# 1-Schematic_SmartTracker.net
KiCad netlist of a schematic drawn in EasyEDA
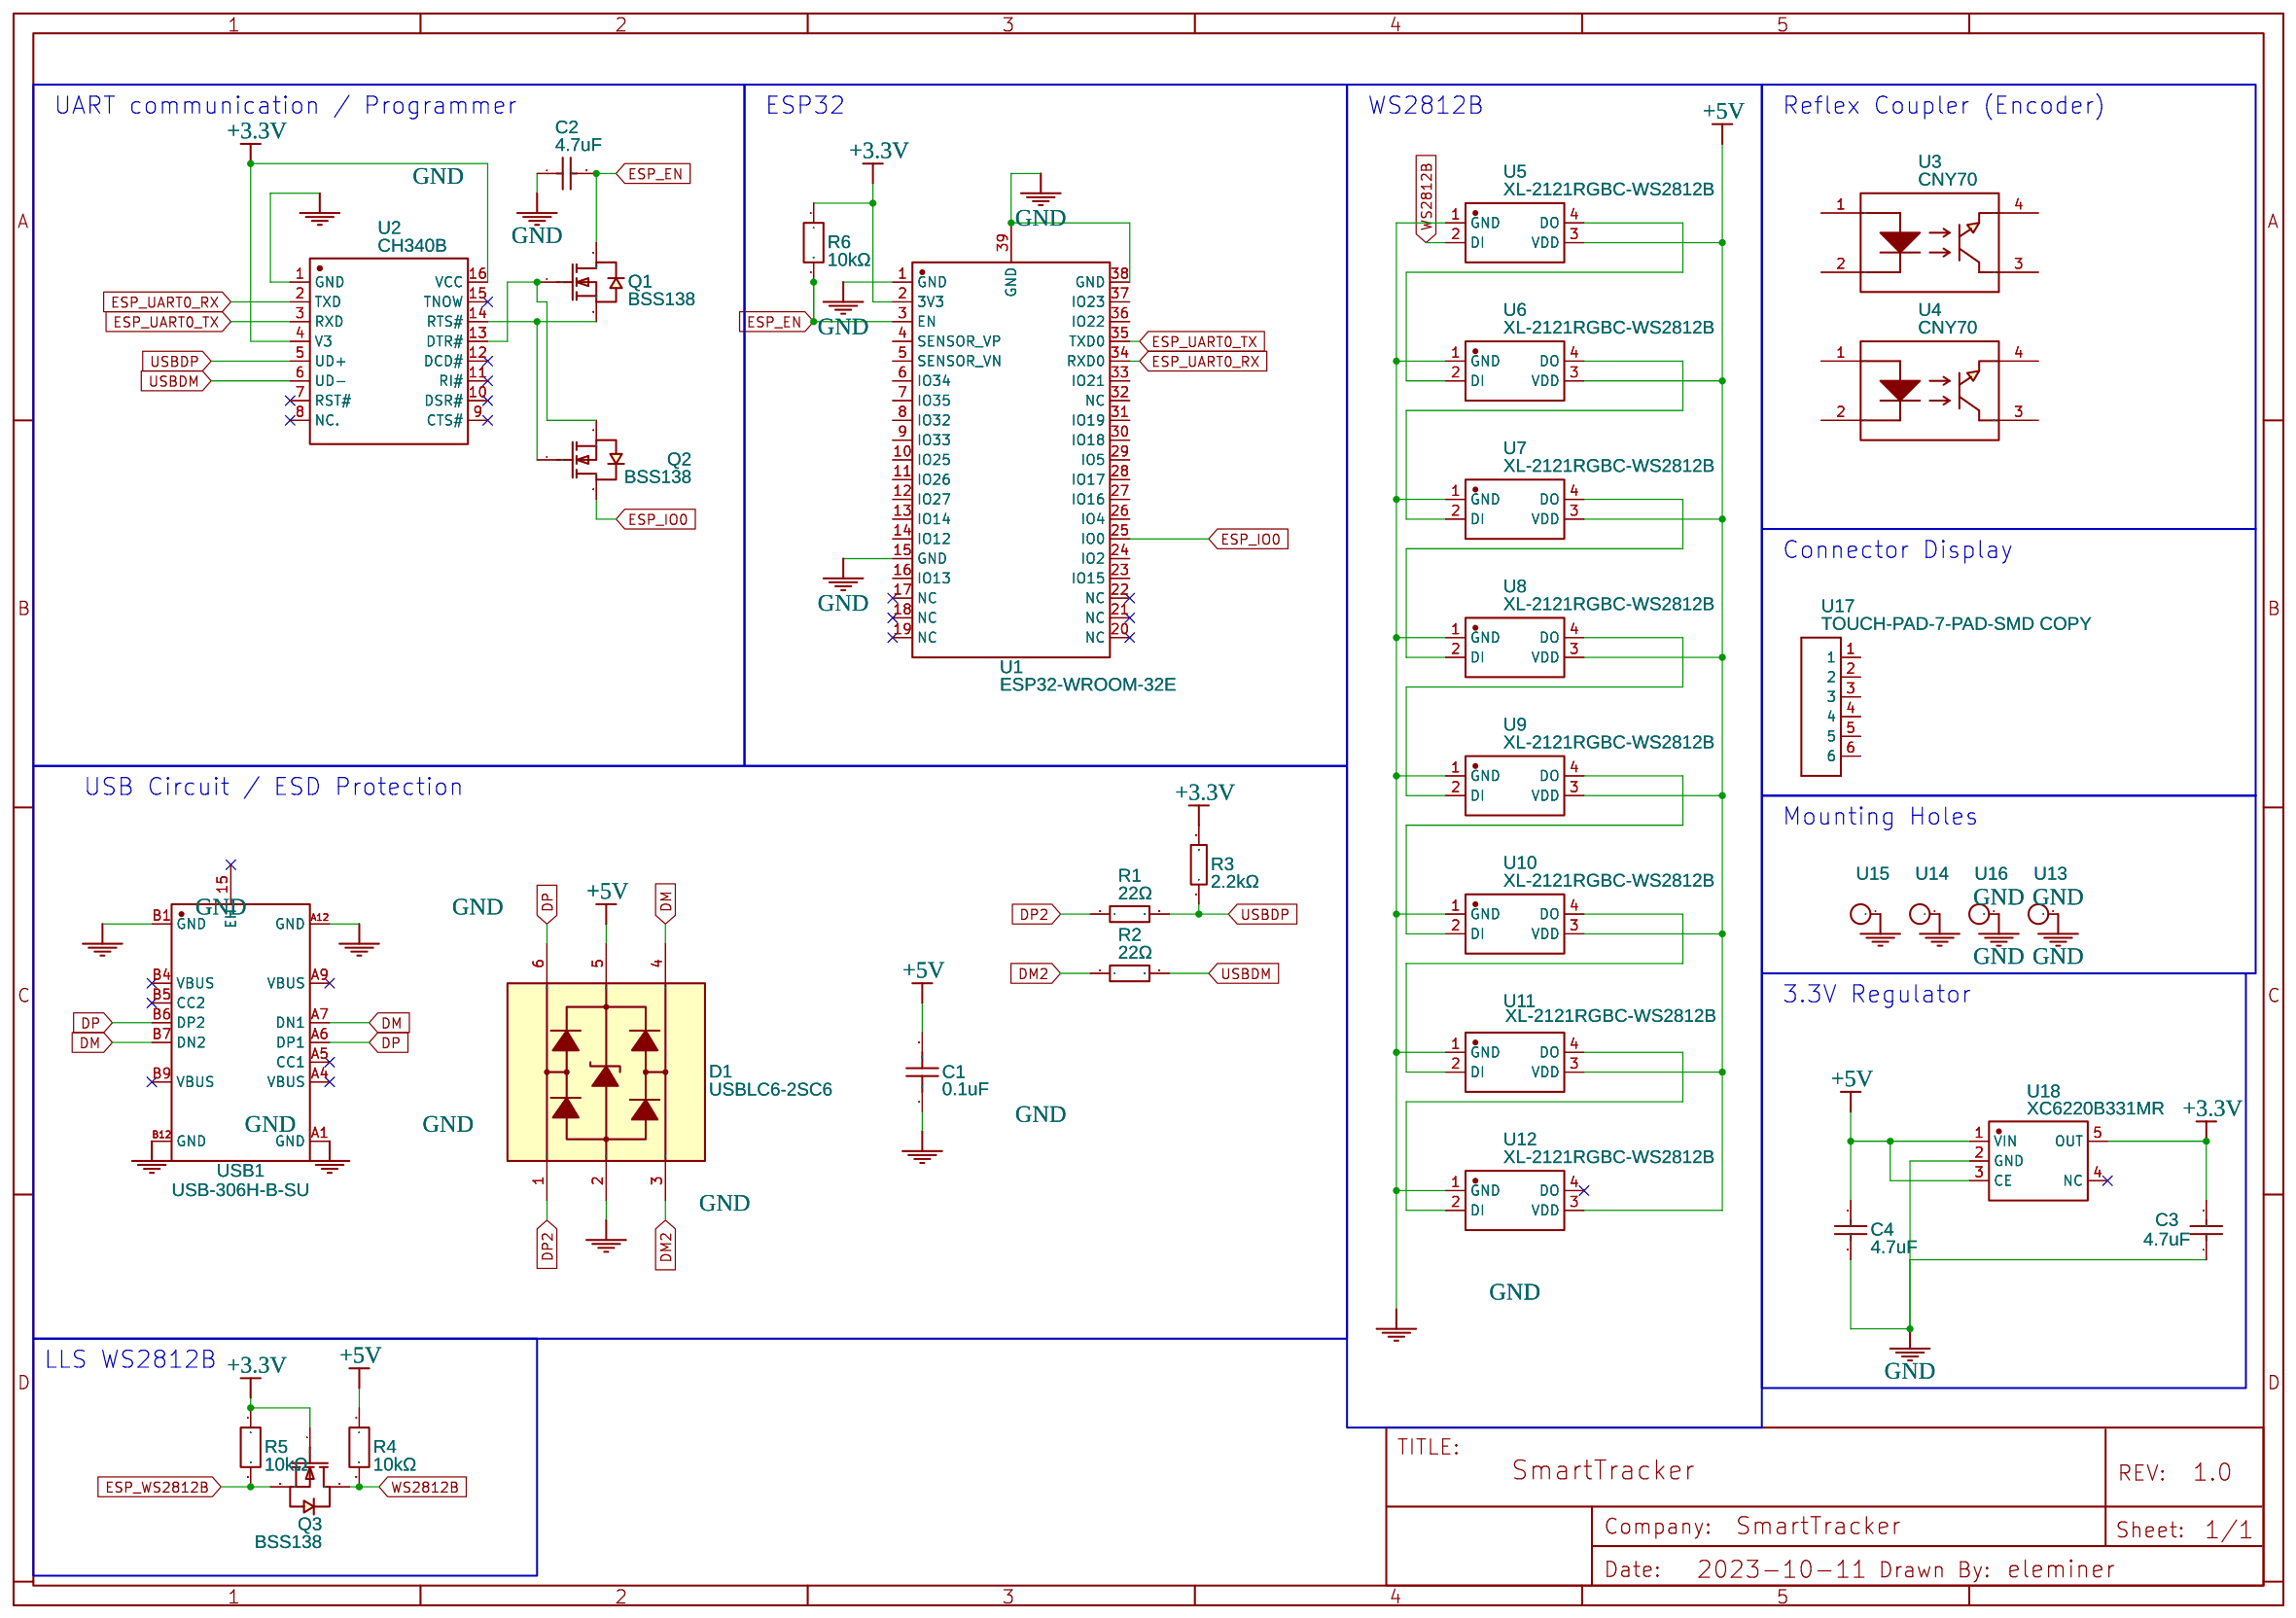
[diagram p0: schematic sheet]

(export (version "E")
  (design (tool "Eeschema 10.0.6"))
  (components
    (comp (ref "C1")
      (value "0.1uF")
      (fields
        (field (name "Manufacturer Part") "0603BB104K500NGT")
        (field (name "Manufacturer") "Knowles(楼氏)")
      )
      (libsource (lib "") (part "0603BB104K500NGT"))
    )
    (comp (ref "C2")
      (value "4.7uF")
      (fields
        (field (name "Manufacturer Part") "CL05A475MP5NRNC")
        (field (name "Manufacturer") "SAMSUNG(三星)")
      )
      (libsource (lib "") (part "CL05A475MP5NRNC_1"))
    )
    (comp (ref "C3")
      (value "4.7uF")
      (fields
        (field (name "Manufacturer Part") "CL05A475MP5NRNC")
        (field (name "Manufacturer") "SAMSUNG(三星)")
      )
      (libsource (lib "") (part "CL05A475MP5NRNC_2"))
    )
    (comp (ref "C4")
      (value "4.7uF")
      (fields
        (field (name "Manufacturer Part") "CL05A475MP5NRNC")
        (field (name "Manufacturer") "SAMSUNG(三星)")
      )
      (libsource (lib "") (part "CL05A475MP5NRNC"))
    )
    (comp (ref "D1")
      (value "USBLC6-2SC6")
      (fields (field (name "Manufacturer") "ST(意法半导体)"))
      (libsource (lib "") (part "USBLC6-2SC6"))
    )
    (comp (ref "Q1")
      (value "BSS138")
      (fields (field (name "Manufacturer") "CJ(江苏长电/长晶)"))
      (libsource (lib "") (part "BSS138_1"))
    )
    (comp (ref "Q2")
      (value "BSS138")
      (fields (field (name "Manufacturer") "CJ(江苏长电/长晶)"))
      (libsource (lib "") (part "BSS138_2"))
    )
    (comp (ref "Q3")
      (value "BSS138")
      (fields (field (name "Manufacturer") "CJ(江苏长电/长晶)"))
      (libsource (lib "") (part "BSS138"))
    )
    (comp (ref "R1")
      (value "22Ω")
      (fields
        (field (name "Manufacturer Part") "0402WGF220JTCE")
        (field (name "Manufacturer") "UNI-ROYAL(厚声)")
      )
      (libsource (lib "") (part "0402WGF220JTCE"))
    )
    (comp (ref "R2")
      (value "22Ω")
      (fields
        (field (name "Manufacturer Part") "0402WGF220JTCE")
        (field (name "Manufacturer") "UNI-ROYAL(厚声)")
      )
      (libsource (lib "") (part "0402WGF220JTCE"))
    )
    (comp (ref "R3")
      (value "2.2kΩ")
      (fields
        (field (name "Manufacturer Part") "0402WGF2201TCE")
        (field (name "Manufacturer") "UNI-ROYAL(厚声)")
      )
      (libsource (lib "") (part "0402WGF2201TCE"))
    )
    (comp (ref "R4")
      (value "10kΩ")
      (fields (field (name "Manufacturer Part") "CR-05FA7---10K") (field (name "Manufacturer") "Viking(光颉)"))
      (libsource (lib "") (part "CR-05FA7---10K"))
    )
    (comp (ref "R5")
      (value "10kΩ")
      (fields (field (name "Manufacturer Part") "CR-05FA7---10K") (field (name "Manufacturer") "Viking(光颉)"))
      (libsource (lib "") (part "CR-05FA7---10K"))
    )
    (comp (ref "R6")
      (value "10kΩ")
      (fields (field (name "Manufacturer Part") "CR-05FA7---10K") (field (name "Manufacturer") "Viking(光颉)"))
      (libsource (lib "") (part "CR-05FA7---10K"))
    )
    (comp (ref "U1")
      (value "ESP32-WROOM-32E")
      (fields
        (field (name "Manufacturer Part") "ESP32-WROOM-32E-N8")
        (field (name "Manufacturer") "ESPRESSIF(乐鑫)")
      )
      (libsource (lib "") (part "ESP32-WROOM-32E(8MB)"))
    )
    (comp (ref "U2")
      (value "CH340B")
      (fields (field (name "Manufacturer") "WCH(南京沁恒)"))
      (libsource (lib "") (part "CH340B"))
    )
    (comp (ref "U3")
      (value "CNY70")
      (fields (field (name "Manufacturer") "VISHAY(威世)"))
      (libsource (lib "") (part "CNY70"))
    )
    (comp (ref "U4")
      (value "CNY70")
      (fields (field (name "Manufacturer") "VISHAY(威世)"))
      (libsource (lib "") (part "CNY70"))
    )
    (comp (ref "U5")
      (value "XL-2121RGBC-WS2812B")
      (fields (field (name "Manufacturer") "XINGLIGHT(成兴光)"))
      (libsource (lib "") (part "XL-2121RGBC-WS2812B"))
    )
    (comp (ref "U6")
      (value "XL-2121RGBC-WS2812B")
      (fields (field (name "Manufacturer") "XINGLIGHT(成兴光)"))
      (libsource (lib "") (part "XL-2121RGBC-WS2812B"))
    )
    (comp (ref "U7")
      (value "XL-2121RGBC-WS2812B")
      (fields (field (name "Manufacturer") "XINGLIGHT(成兴光)"))
      (libsource (lib "") (part "XL-2121RGBC-WS2812B"))
    )
    (comp (ref "U8")
      (value "XL-2121RGBC-WS2812B")
      (fields (field (name "Manufacturer") "XINGLIGHT(成兴光)"))
      (libsource (lib "") (part "XL-2121RGBC-WS2812B"))
    )
    (comp (ref "U9")
      (value "XL-2121RGBC-WS2812B")
      (fields (field (name "Manufacturer") "XINGLIGHT(成兴光)"))
      (libsource (lib "") (part "XL-2121RGBC-WS2812B"))
    )
    (comp (ref "U10")
      (value "XL-2121RGBC-WS2812B")
      (fields (field (name "Manufacturer") "XINGLIGHT(成兴光)"))
      (libsource (lib "") (part "XL-2121RGBC-WS2812B"))
    )
    (comp (ref "U11")
      (value "XL-2121RGBC-WS2812B")
      (fields (field (name "Manufacturer") "XINGLIGHT(成兴光)"))
      (libsource (lib "") (part "XL-2121RGBC-WS2812B"))
    )
    (comp (ref "U12")
      (value "XL-2121RGBC-WS2812B")
      (fields (field (name "Manufacturer") "XINGLIGHT(成兴光)"))
      (libsource (lib "") (part "XL-2121RGBC-WS2812B"))
    )
    (comp (ref "U13") (value "NO") (libsource (lib "") (part "M3 CLR HOLE")))
    (comp (ref "U14") (value "NO") (libsource (lib "") (part "M3 CLR HOLE")))
    (comp (ref "U15") (value "NO") (libsource (lib "") (part "M3 CLR HOLE")))
    (comp (ref "U16") (value "NO") (libsource (lib "") (part "M3 CLR HOLE")))
    (comp (ref "U17")
      (value "TOUCH-PAD-7-PAD-SMD COPY")
      (libsource (lib "") (part "TOUCH-PAD-7-PAD-SMD COPY"))
    )
    (comp (ref "U18")
      (value "XC6220B331MR")
      (fields (field (name "Manufacturer") "TECH PUBLIC(台舟)"))
      (libsource (lib "") (part "XC6220B331MR"))
    )
    (comp (ref "USB1")
      (value "USB-306H-B-SU")
      (fields (field (name "Manufacturer") "HOOYA"))
      (libsource (lib "") (part "USB-306H-B-SU"))
    )
  )
  (nets
    (net (code "1") (name "+3.3V") (class "Default")
      (node (ref "C3") (pin "2") (pinfunction "2_2") (pintype "input"))
      (node (ref "Q3") (pin "1") (pinfunction "G_1") (pintype "unspecified"))
      (node (ref "R3") (pin "2") (pinfunction "2_2") (pintype "input"))
      (node (ref "R5") (pin "1") (pinfunction "1_1") (pintype "unspecified"))
      (node (ref "R6") (pin "1") (pinfunction "1_1") (pintype "unspecified"))
      (node (ref "U1") (pin "2") (pinfunction "3V3_2") (pintype "unspecified"))
      (node (ref "U18") (pin "5") (pinfunction "OUT_5") (pintype "unspecified"))
      (node (ref "U2") (pin "16") (pinfunction "VCC_16") (pintype "unspecified"))
      (node (ref "U2") (pin "4") (pinfunction "V3_4") (pintype "unspecified"))
    )
    (net (code "2") (name "+5V") (class "Default")
      (node (ref "C1") (pin "2") (pinfunction "2_2") (pintype "unspecified"))
      (node (ref "C4") (pin "1") (pinfunction "1_1") (pintype "input"))
      (node (ref "D1") (pin "5") (pinfunction "5_5") (pintype "input"))
      (node (ref "R4") (pin "1") (pinfunction "1_1") (pintype "unspecified"))
      (node (ref "U10") (pin "3") (pinfunction "VDD_3") (pintype "unspecified"))
      (node (ref "U11") (pin "3") (pinfunction "VDD_3") (pintype "unspecified"))
      (node (ref "U12") (pin "3") (pinfunction "VDD_3") (pintype "unspecified"))
      (node (ref "U18") (pin "1") (pinfunction "VIN_1") (pintype "unspecified"))
      (node (ref "U18") (pin "3") (pinfunction "CE_3") (pintype "unspecified"))
      (node (ref "U5") (pin "3") (pinfunction "VDD_3") (pintype "unspecified"))
      (node (ref "U6") (pin "3") (pinfunction "VDD_3") (pintype "unspecified"))
      (node (ref "U7") (pin "3") (pinfunction "VDD_3") (pintype "unspecified"))
      (node (ref "U8") (pin "3") (pinfunction "VDD_3") (pintype "unspecified"))
      (node (ref "U9") (pin "3") (pinfunction "VDD_3") (pintype "unspecified"))
    )
    (net (code "3") (name "DM") (class "Default")
      (node (ref "D1") (pin "4") (pinfunction "4_4") (pintype "input"))
      (node (ref "USB1") (pin "A7") (pinfunction "DN1_A7") (pintype "unspecified"))
      (node (ref "USB1") (pin "B7") (pinfunction "DN2_B7") (pintype "unspecified"))
    )
    (net (code "4") (name "DM2") (class "Default")
      (node (ref "D1") (pin "3") (pinfunction "3_3") (pintype "input"))
      (node (ref "R2") (pin "1") (pinfunction "1_1") (pintype "input"))
    )
    (net (code "5") (name "DP") (class "Default")
      (node (ref "D1") (pin "6") (pinfunction "6_6") (pintype "input"))
      (node (ref "USB1") (pin "A6") (pinfunction "DP1_A6") (pintype "unspecified"))
      (node (ref "USB1") (pin "B6") (pinfunction "DP2_B6") (pintype "unspecified"))
    )
    (net (code "6") (name "DP2") (class "Default")
      (node (ref "D1") (pin "1") (pinfunction "1_1") (pintype "input"))
      (node (ref "R1") (pin "1") (pinfunction "1_1") (pintype "input"))
    )
    (net (code "7") (name "ESP_EN") (class "Default")
      (node (ref "C2") (pin "2") (pinfunction "2_2") (pintype "input"))
      (node (ref "Q1") (pin "3") (pinfunction "D_3") (pintype "unspecified"))
      (node (ref "R6") (pin "2") (pinfunction "2_2") (pintype "unspecified"))
      (node (ref "U1") (pin "3") (pinfunction "EN_3") (pintype "unspecified"))
    )
    (net (code "8") (name "ESP_IO0") (class "Default")
      (node (ref "Q2") (pin "3") (pinfunction "D_3") (pintype "unspecified"))
      (node (ref "U1") (pin "25") (pinfunction "IO0_25") (pintype "unspecified"))
    )
    (net (code "9") (name "ESP_UART0_RX") (class "Default")
      (node (ref "U1") (pin "34") (pinfunction "RXD0_34") (pintype "unspecified"))
      (node (ref "U2") (pin "2") (pinfunction "TXD_2") (pintype "unspecified"))
    )
    (net (code "10") (name "ESP_UART0_TX") (class "Default")
      (node (ref "U1") (pin "35") (pinfunction "TXD0_35") (pintype "unspecified"))
      (node (ref "U2") (pin "3") (pinfunction "RXD_3") (pintype "unspecified"))
    )
    (net (code "11") (name "ESP_WS2812B") (class "Default")
      (node (ref "Q3") (pin "2") (pinfunction "S_2") (pintype "unspecified"))
      (node (ref "R5") (pin "2") (pinfunction "2_2") (pintype "unspecified"))
    )
    (net (code "12") (name "GND") (class "Default")
      (node (ref "C1") (pin "1") (pinfunction "1_1") (pintype "unspecified"))
      (node (ref "C2") (pin "1") (pinfunction "1_1") (pintype "input"))
      (node (ref "C3") (pin "1") (pinfunction "1_1") (pintype "input"))
      (node (ref "C4") (pin "2") (pinfunction "2_2") (pintype "input"))
      (node (ref "D1") (pin "2") (pinfunction "2_2") (pintype "input"))
      (node (ref "U1") (pin "1") (pinfunction "GND_1") (pintype "unspecified"))
      (node (ref "U1") (pin "15") (pinfunction "GND_15") (pintype "unspecified"))
      (node (ref "U1") (pin "38") (pinfunction "GND_38") (pintype "unspecified"))
      (node (ref "U1") (pin "39") (pinfunction "GND_39") (pintype "unspecified"))
      (node (ref "U10") (pin "1") (pinfunction "GND_1") (pintype "unspecified"))
      (node (ref "U11") (pin "1") (pinfunction "GND_1") (pintype "unspecified"))
      (node (ref "U12") (pin "1") (pinfunction "GND_1") (pintype "unspecified"))
      (node (ref "U13") (pin "1") (pinfunction "1_1") (pintype "unspecified"))
      (node (ref "U14") (pin "1") (pinfunction "1_1") (pintype "unspecified"))
      (node (ref "U15") (pin "1") (pinfunction "1_1") (pintype "unspecified"))
      (node (ref "U16") (pin "1") (pinfunction "1_1") (pintype "unspecified"))
      (node (ref "U18") (pin "2") (pinfunction "GND_2") (pintype "unspecified"))
      (node (ref "U2") (pin "1") (pinfunction "GND_1") (pintype "unspecified"))
      (node (ref "U5") (pin "1") (pinfunction "GND_1") (pintype "unspecified"))
      (node (ref "U6") (pin "1") (pinfunction "GND_1") (pintype "unspecified"))
      (node (ref "U7") (pin "1") (pinfunction "GND_1") (pintype "unspecified"))
      (node (ref "U8") (pin "1") (pinfunction "GND_1") (pintype "unspecified"))
      (node (ref "U9") (pin "1") (pinfunction "GND_1") (pintype "unspecified"))
      (node (ref "USB1") (pin "A1") (pinfunction "GND_A1") (pintype "unspecified"))
      (node (ref "USB1") (pin "A12") (pinfunction "GND_A12") (pintype "unspecified"))
      (node (ref "USB1") (pin "B1") (pinfunction "GND_B1") (pintype "unspecified"))
      (node (ref "USB1") (pin "B12") (pinfunction "GND_B12") (pintype "unspecified"))
    )
    (net (code "13") (name "Net-(Q1-G)") (class "Default")
      (node (ref "Q1") (pin "1") (pinfunction "G_1") (pintype "unspecified"))
      (node (ref "Q2") (pin "2") (pinfunction "S_2") (pintype "unspecified"))
      (node (ref "U2") (pin "13") (pinfunction "DTR#_13") (pintype "unspecified"))
    )
    (net (code "14") (name "Net-(Q1-S)") (class "Default")
      (node (ref "Q1") (pin "2") (pinfunction "S_2") (pintype "unspecified"))
      (node (ref "Q2") (pin "1") (pinfunction "G_1") (pintype "unspecified"))
      (node (ref "U2") (pin "14") (pinfunction "RTS#_14") (pintype "unspecified"))
    )
    (net (code "15") (name "Net-(U5-DO)") (class "Default")
      (node (ref "U5") (pin "4") (pinfunction "DO_4") (pintype "unspecified"))
      (node (ref "U6") (pin "2") (pinfunction "DI_2") (pintype "unspecified"))
    )
    (net (code "16") (name "Net-(U6-DO)") (class "Default")
      (node (ref "U6") (pin "4") (pinfunction "DO_4") (pintype "unspecified"))
      (node (ref "U7") (pin "2") (pinfunction "DI_2") (pintype "unspecified"))
    )
    (net (code "17") (name "Net-(U7-DO)") (class "Default")
      (node (ref "U7") (pin "4") (pinfunction "DO_4") (pintype "unspecified"))
      (node (ref "U8") (pin "2") (pinfunction "DI_2") (pintype "unspecified"))
    )
    (net (code "18") (name "Net-(U8-DO)") (class "Default")
      (node (ref "U8") (pin "4") (pinfunction "DO_4") (pintype "unspecified"))
      (node (ref "U9") (pin "2") (pinfunction "DI_2") (pintype "unspecified"))
    )
    (net (code "19") (name "Net-(U10-DI)") (class "Default")
      (node (ref "U10") (pin "2") (pinfunction "DI_2") (pintype "unspecified"))
      (node (ref "U9") (pin "4") (pinfunction "DO_4") (pintype "unspecified"))
    )
    (net (code "20") (name "Net-(U10-DO)") (class "Default")
      (node (ref "U10") (pin "4") (pinfunction "DO_4") (pintype "unspecified"))
      (node (ref "U11") (pin "2") (pinfunction "DI_2") (pintype "unspecified"))
    )
    (net (code "21") (name "Net-(U11-DO)") (class "Default")
      (node (ref "U11") (pin "4") (pinfunction "DO_4") (pintype "unspecified"))
      (node (ref "U12") (pin "2") (pinfunction "DI_2") (pintype "unspecified"))
    )
    (net (code "22") (name "USBDM") (class "Default")
      (node (ref "R2") (pin "2") (pinfunction "2_2") (pintype "input"))
      (node (ref "U2") (pin "6") (pinfunction "UD-_6") (pintype "unspecified"))
    )
    (net (code "23") (name "USBDP") (class "Default")
      (node (ref "R1") (pin "2") (pinfunction "2_2") (pintype "input"))
      (node (ref "R3") (pin "1") (pinfunction "1_1") (pintype "input"))
      (node (ref "U2") (pin "5") (pinfunction "UD+_5") (pintype "unspecified"))
    )
    (net (code "24") (name "WS2812B") (class "Default")
      (node (ref "Q3") (pin "3") (pinfunction "D_3") (pintype "unspecified"))
      (node (ref "R4") (pin "2") (pinfunction "2_2") (pintype "unspecified"))
      (node (ref "U5") (pin "2") (pinfunction "DI_2") (pintype "unspecified"))
    )
    (net (code "25") (name "unconnected-(U1-IO2-Pad24)") (class "Default")
      (node (ref "U1") (pin "24") (pinfunction "IO2_24") (pintype "unspecified"))
    )
    (net (code "26") (name "unconnected-(U1-IO4-Pad26)") (class "Default")
      (node (ref "U1") (pin "26") (pinfunction "IO4_26") (pintype "unspecified"))
    )
    (net (code "27") (name "unconnected-(U1-IO5-Pad29)") (class "Default")
      (node (ref "U1") (pin "29") (pinfunction "IO5_29") (pintype "unspecified"))
    )
    (net (code "28") (name "unconnected-(U1-IO12-Pad14)") (class "Default")
      (node (ref "U1") (pin "14") (pinfunction "IO12_14") (pintype "unspecified"))
    )
    (net (code "29") (name "unconnected-(U1-IO13-Pad16)") (class "Default")
      (node (ref "U1") (pin "16") (pinfunction "IO13_16") (pintype "unspecified"))
    )
    (net (code "30") (name "unconnected-(U1-IO14-Pad13)") (class "Default")
      (node (ref "U1") (pin "13") (pinfunction "IO14_13") (pintype "unspecified"))
    )
    (net (code "31") (name "unconnected-(U1-IO15-Pad23)") (class "Default")
      (node (ref "U1") (pin "23") (pinfunction "IO15_23") (pintype "unspecified"))
    )
    (net (code "32") (name "unconnected-(U1-IO16-Pad27)") (class "Default")
      (node (ref "U1") (pin "27") (pinfunction "IO16_27") (pintype "unspecified"))
    )
    (net (code "33") (name "unconnected-(U1-IO17-Pad28)") (class "Default")
      (node (ref "U1") (pin "28") (pinfunction "IO17_28") (pintype "unspecified"))
    )
    (net (code "34") (name "unconnected-(U1-IO18-Pad30)") (class "Default")
      (node (ref "U1") (pin "30") (pinfunction "IO18_30") (pintype "unspecified"))
    )
    (net (code "35") (name "unconnected-(U1-IO19-Pad31)") (class "Default")
      (node (ref "U1") (pin "31") (pinfunction "IO19_31") (pintype "unspecified"))
    )
    (net (code "36") (name "unconnected-(U1-IO21-Pad33)") (class "Default")
      (node (ref "U1") (pin "33") (pinfunction "IO21_33") (pintype "unspecified"))
    )
    (net (code "37") (name "unconnected-(U1-IO22-Pad36)") (class "Default")
      (node (ref "U1") (pin "36") (pinfunction "IO22_36") (pintype "unspecified"))
    )
    (net (code "38") (name "unconnected-(U1-IO23-Pad37)") (class "Default")
      (node (ref "U1") (pin "37") (pinfunction "IO23_37") (pintype "unspecified"))
    )
    (net (code "39") (name "unconnected-(U1-IO25-Pad10)") (class "Default")
      (node (ref "U1") (pin "10") (pinfunction "IO25_10") (pintype "unspecified"))
    )
    (net (code "40") (name "unconnected-(U1-IO26-Pad11)") (class "Default")
      (node (ref "U1") (pin "11") (pinfunction "IO26_11") (pintype "unspecified"))
    )
    (net (code "41") (name "unconnected-(U1-IO27-Pad12)") (class "Default")
      (node (ref "U1") (pin "12") (pinfunction "IO27_12") (pintype "unspecified"))
    )
    (net (code "42") (name "unconnected-(U1-IO32-Pad8)") (class "Default")
      (node (ref "U1") (pin "8") (pinfunction "IO32_8") (pintype "unspecified"))
    )
    (net (code "43") (name "unconnected-(U1-IO33-Pad9)") (class "Default")
      (node (ref "U1") (pin "9") (pinfunction "IO33_9") (pintype "unspecified"))
    )
    (net (code "44") (name "unconnected-(U1-IO34-Pad6)") (class "Default")
      (node (ref "U1") (pin "6") (pinfunction "IO34_6") (pintype "unspecified"))
    )
    (net (code "45") (name "unconnected-(U1-IO35-Pad7)") (class "Default")
      (node (ref "U1") (pin "7") (pinfunction "IO35_7") (pintype "unspecified"))
    )
    (net (code "46") (name "unconnected-(U1-NC-Pad17)") (class "Default")
      (node (ref "U1") (pin "17") (pinfunction "NC_17") (pintype "unspecified+no_connect"))
    )
    (net (code "47") (name "unconnected-(U1-NC-Pad18)") (class "Default")
      (node (ref "U1") (pin "18") (pinfunction "NC_18") (pintype "unspecified+no_connect"))
    )
    (net (code "48") (name "unconnected-(U1-NC-Pad19)") (class "Default")
      (node (ref "U1") (pin "19") (pinfunction "NC_19") (pintype "unspecified+no_connect"))
    )
    (net (code "49") (name "unconnected-(U1-NC-Pad20)") (class "Default")
      (node (ref "U1") (pin "20") (pinfunction "NC_20") (pintype "unspecified+no_connect"))
    )
    (net (code "50") (name "unconnected-(U1-NC-Pad21)") (class "Default")
      (node (ref "U1") (pin "21") (pinfunction "NC_21") (pintype "unspecified+no_connect"))
    )
    (net (code "51") (name "unconnected-(U1-NC-Pad22)") (class "Default")
      (node (ref "U1") (pin "22") (pinfunction "NC_22") (pintype "unspecified+no_connect"))
    )
    (net (code "52") (name "unconnected-(U1-NC-Pad32)") (class "Default")
      (node (ref "U1") (pin "32") (pinfunction "NC_32") (pintype "unspecified"))
    )
    (net (code "53") (name "unconnected-(U1-SENSOR_VN-Pad5)") (class "Default")
      (node (ref "U1") (pin "5") (pinfunction "SENSOR_VN_5") (pintype "unspecified"))
    )
    (net (code "54") (name "unconnected-(U1-SENSOR_VP-Pad4)") (class "Default")
      (node (ref "U1") (pin "4") (pinfunction "SENSOR_VP_4") (pintype "unspecified"))
    )
    (net (code "55") (name "unconnected-(U2-CTS#-Pad9)") (class "Default")
      (node (ref "U2") (pin "9") (pinfunction "CTS#_9") (pintype "unspecified+no_connect"))
    )
    (net (code "56") (name "unconnected-(U2-DCD#-Pad12)") (class "Default")
      (node (ref "U2") (pin "12") (pinfunction "DCD#_12") (pintype "unspecified+no_connect"))
    )
    (net (code "57") (name "unconnected-(U2-DSR#-Pad10)") (class "Default")
      (node (ref "U2") (pin "10") (pinfunction "DSR#_10") (pintype "unspecified+no_connect"))
    )
    (net (code "58") (name "unconnected-(U2-NC.-Pad8)") (class "Default")
      (node (ref "U2") (pin "8") (pinfunction "NC._8") (pintype "unspecified+no_connect"))
    )
    (net (code "59") (name "unconnected-(U2-RI#-Pad11)") (class "Default")
      (node (ref "U2") (pin "11") (pinfunction "RI#_11") (pintype "unspecified+no_connect"))
    )
    (net (code "60") (name "unconnected-(U2-RST#-Pad7)") (class "Default")
      (node (ref "U2") (pin "7") (pinfunction "RST#_7") (pintype "unspecified+no_connect"))
    )
    (net (code "61") (name "unconnected-(U2-TNOW-Pad15)") (class "Default")
      (node (ref "U2") (pin "15") (pinfunction "TNOW_15") (pintype "unspecified+no_connect"))
    )
    (net (code "62") (name "unconnected-(U3-Pad1)") (class "Default")
      (node (ref "U3") (pin "1") (pinfunction "1_1") (pintype "input"))
    )
    (net (code "63") (name "unconnected-(U3-Pad2)") (class "Default")
      (node (ref "U3") (pin "2") (pinfunction "2_2") (pintype "input"))
    )
    (net (code "64") (name "unconnected-(U3-Pad3)") (class "Default")
      (node (ref "U3") (pin "3") (pinfunction "3_3") (pintype "input"))
    )
    (net (code "65") (name "unconnected-(U3-Pad4)") (class "Default")
      (node (ref "U3") (pin "4") (pinfunction "4_4") (pintype "input"))
    )
    (net (code "66") (name "unconnected-(U4-Pad1)") (class "Default")
      (node (ref "U4") (pin "1") (pinfunction "1_1") (pintype "input"))
    )
    (net (code "67") (name "unconnected-(U4-Pad2)") (class "Default")
      (node (ref "U4") (pin "2") (pinfunction "2_2") (pintype "input"))
    )
    (net (code "68") (name "unconnected-(U4-Pad3)") (class "Default")
      (node (ref "U4") (pin "3") (pinfunction "3_3") (pintype "input"))
    )
    (net (code "69") (name "unconnected-(U4-Pad4)") (class "Default")
      (node (ref "U4") (pin "4") (pinfunction "4_4") (pintype "input"))
    )
    (net (code "70") (name "unconnected-(U12-DO-Pad4)") (class "Default")
      (node (ref "U12") (pin "4") (pinfunction "DO_4") (pintype "unspecified+no_connect"))
    )
    (net (code "71") (name "unconnected-(U17-Pad1)") (class "Default")
      (node (ref "U17") (pin "1") (pinfunction "1_1") (pintype "unspecified"))
    )
    (net (code "72") (name "unconnected-(U17-Pad2)") (class "Default")
      (node (ref "U17") (pin "2") (pinfunction "2_2") (pintype "unspecified"))
    )
    (net (code "73") (name "unconnected-(U17-Pad3)") (class "Default")
      (node (ref "U17") (pin "3") (pinfunction "3_3") (pintype "unspecified"))
    )
    (net (code "74") (name "unconnected-(U17-Pad4)") (class "Default")
      (node (ref "U17") (pin "4") (pinfunction "4_4") (pintype "unspecified"))
    )
    (net (code "75") (name "unconnected-(U17-Pad5)") (class "Default")
      (node (ref "U17") (pin "5") (pinfunction "5_5") (pintype "unspecified"))
    )
    (net (code "76") (name "unconnected-(U17-Pad6)") (class "Default")
      (node (ref "U17") (pin "6") (pinfunction "6_6") (pintype "unspecified"))
    )
    (net (code "77") (name "unconnected-(U18-NC-Pad4)") (class "Default")
      (node (ref "U18") (pin "4") (pinfunction "NC_4") (pintype "unspecified+no_connect"))
    )
    (net (code "78") (name "unconnected-(USB1-CC1-PadA5)") (class "Default")
      (node (ref "USB1") (pin "A5") (pinfunction "CC1_A5") (pintype "unspecified+no_connect"))
    )
    (net (code "79") (name "unconnected-(USB1-CC2-PadB5)") (class "Default")
      (node (ref "USB1") (pin "B5") (pinfunction "CC2_B5") (pintype "unspecified+no_connect"))
    )
    (net (code "80") (name "unconnected-(USB1-EH-Pad15)") (class "Default")
      (node (ref "USB1") (pin "15") (pinfunction "EH_15") (pintype "unspecified+no_connect"))
    )
    (net (code "81") (name "unconnected-(USB1-VBUS-PadA4)") (class "Default")
      (node (ref "USB1") (pin "A4") (pinfunction "VBUS_A4") (pintype "unspecified+no_connect"))
    )
    (net (code "82") (name "unconnected-(USB1-VBUS-PadA9)") (class "Default")
      (node (ref "USB1") (pin "A9") (pinfunction "VBUS_A9") (pintype "unspecified+no_connect"))
    )
    (net (code "83") (name "unconnected-(USB1-VBUS-PadB4)") (class "Default")
      (node (ref "USB1") (pin "B4") (pinfunction "VBUS_B4") (pintype "unspecified+no_connect"))
    )
    (net (code "84") (name "unconnected-(USB1-VBUS-PadB9)") (class "Default")
      (node (ref "USB1") (pin "B9") (pinfunction "VBUS_B9") (pintype "unspecified+no_connect"))
    )
  )
)
